# BP_devboard.net
KiCad netlist of a schematic drawn in EAGLE
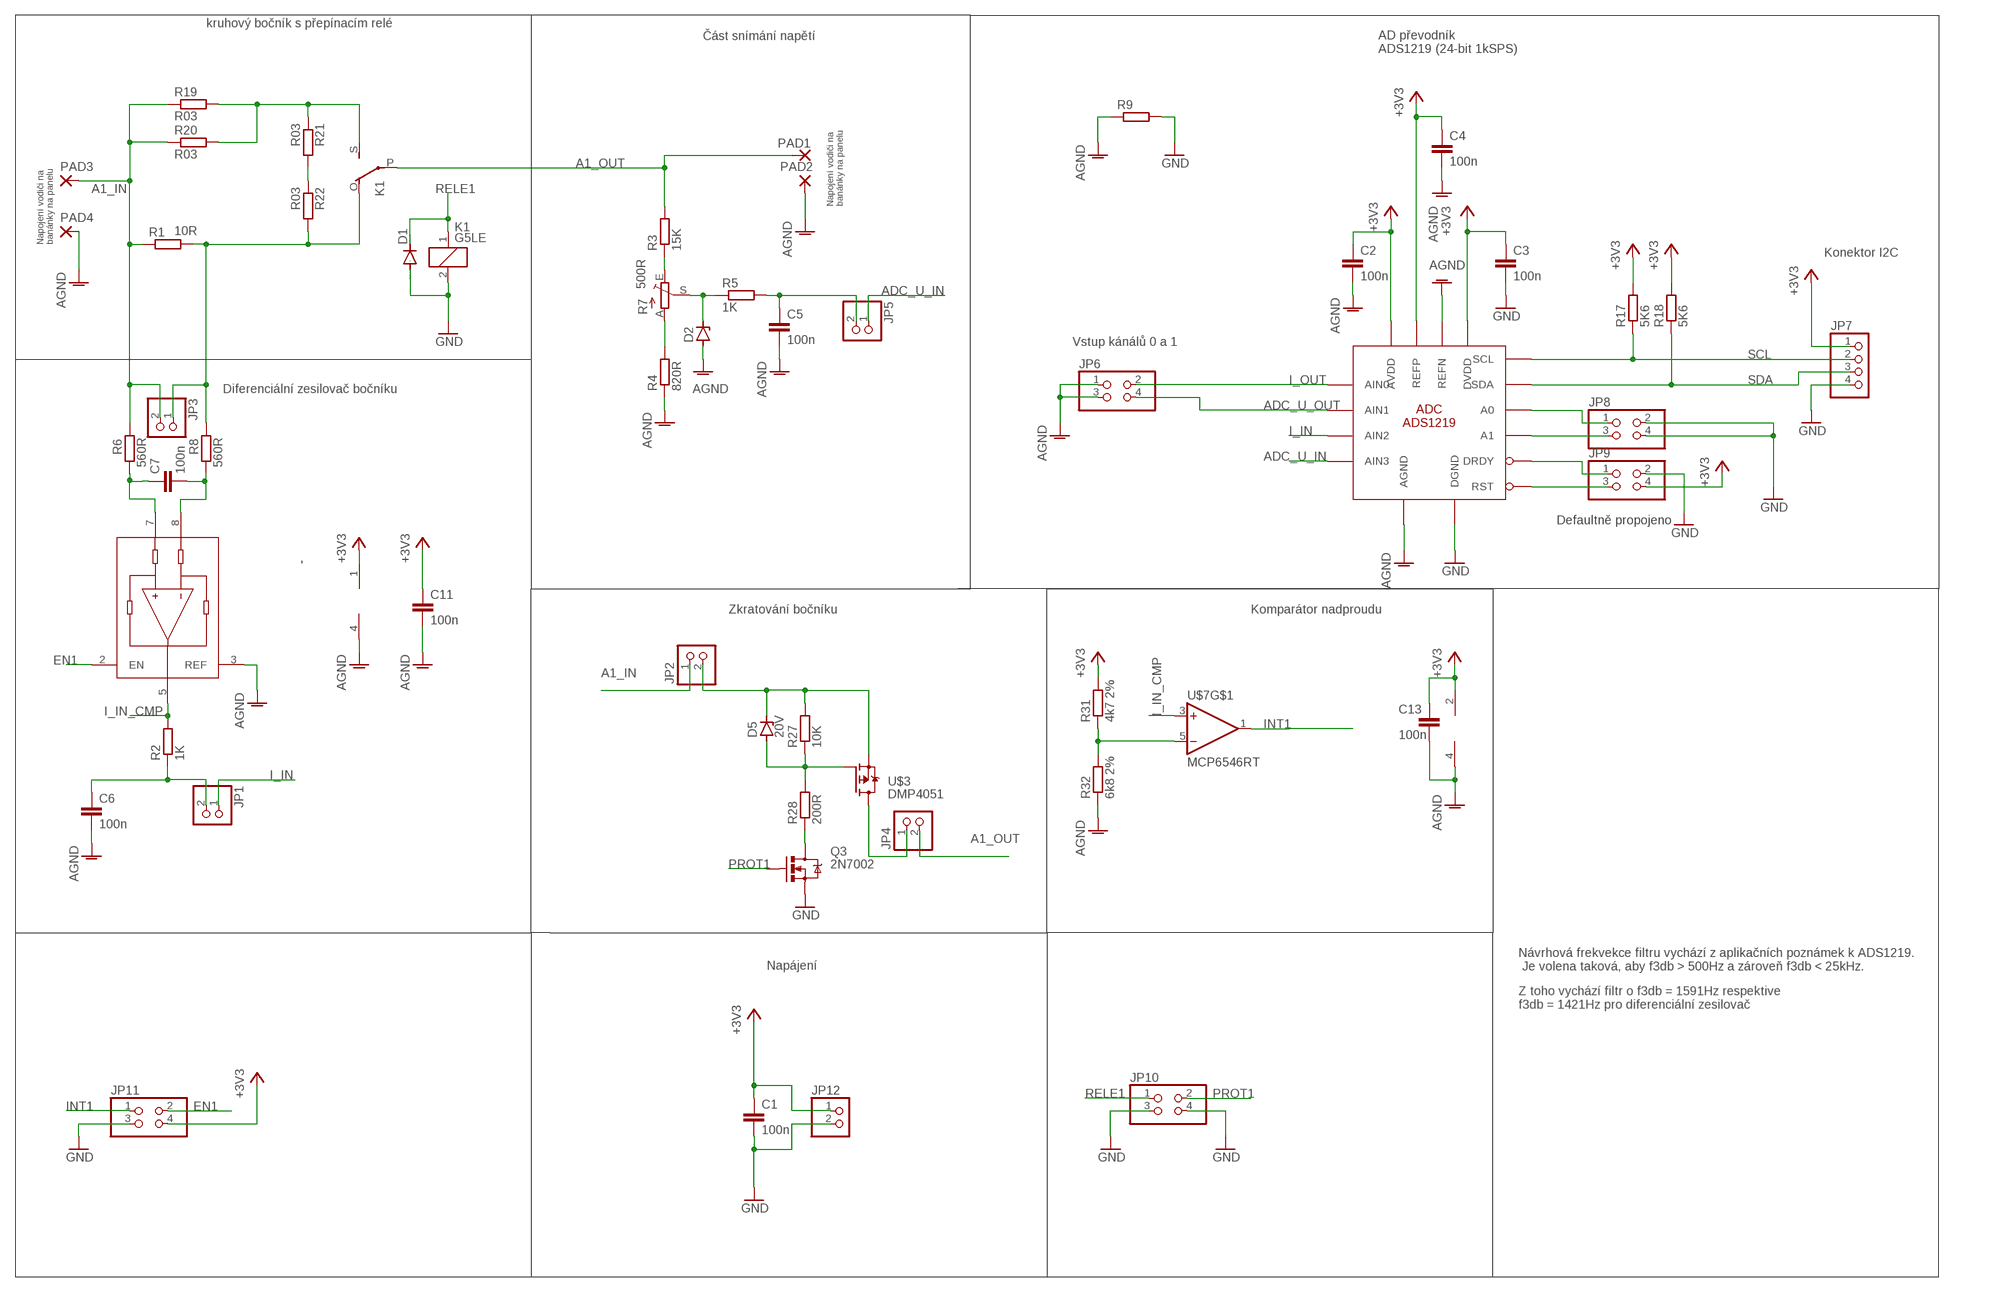
[diagram p0: schematic, sheet 1]

(export (version "E")
  (design (tool "Eeschema 10.0.6"))
  (components
    (comp (ref "C1")
      (value "100n")
      (footprint "eagle-import:C0805")
      (libsource (lib "eagle-import") (part "C-EUC0805"))
    )
    (comp (ref "C2")
      (value "100n")
      (footprint "eagle-import:C0805")
      (libsource (lib "eagle-import") (part "C-EUC0805"))
    )
    (comp (ref "C3")
      (value "100n")
      (footprint "eagle-import:C0805")
      (libsource (lib "eagle-import") (part "C-EUC0805"))
    )
    (comp (ref "C4")
      (value "100n")
      (footprint "eagle-import:C0805")
      (libsource (lib "eagle-import") (part "C-EUC0805"))
    )
    (comp (ref "C5")
      (value "100n")
      (footprint "eagle-import:C0805")
      (libsource (lib "eagle-import") (part "C-EUC0805"))
    )
    (comp (ref "C6")
      (value "100n")
      (footprint "eagle-import:C0805")
      (libsource (lib "eagle-import") (part "C-EUC0805"))
    )
    (comp (ref "C7")
      (value "100n")
      (footprint "eagle-import:C0805")
      (libsource (lib "eagle-import") (part "C-EUC0805"))
    )
    (comp (ref "C11")
      (value "100n")
      (footprint "eagle-import:C0805")
      (libsource (lib "eagle-import") (part "C-EUC0805"))
    )
    (comp (ref "C13")
      (value "100n")
      (footprint "eagle-import:C0805")
      (libsource (lib "eagle-import") (part "C-EUC0805"))
    )
    (comp (ref "D1")
      (value "DIODE-MELF-MLL41")
      (footprint "eagle-import:MELF-MLL41")
      (libsource (lib "eagle-import") (part "DIODE-MELF-MLL41"))
    )
    (comp (ref "D2")
      (value "ZENER-DIODESOD80C")
      (footprint "eagle-import:SOD80C")
      (libsource (lib "eagle-import") (part "ZENER-DIODESOD80C"))
    )
    (comp (ref "D5")
      (value "20V")
      (footprint "eagle-import:SMB")
      (libsource (lib "eagle-import") (part "ZENER-DIODESMB"))
    )
    (comp (ref "JP1")
      (value "PINHD-1X2")
      (footprint "eagle-import:1X02")
      (libsource (lib "eagle-import") (part "PINHD-1X2"))
    )
    (comp (ref "JP2")
      (value "PINHD-1X2")
      (footprint "eagle-import:1X02")
      (libsource (lib "eagle-import") (part "PINHD-1X2"))
    )
    (comp (ref "JP3")
      (value "PINHD-1X2")
      (footprint "eagle-import:1X02")
      (libsource (lib "eagle-import") (part "PINHD-1X2"))
    )
    (comp (ref "JP4")
      (value "PINHD-1X2")
      (footprint "eagle-import:1X02")
      (libsource (lib "eagle-import") (part "PINHD-1X2"))
    )
    (comp (ref "JP5")
      (value "PINHD-1X2")
      (footprint "eagle-import:1X02")
      (libsource (lib "eagle-import") (part "PINHD-1X2"))
    )
    (comp (ref "JP6")
      (value "PINHD-2X2")
      (footprint "eagle-import:2X02")
      (libsource (lib "eagle-import") (part "PINHD-2X2"))
    )
    (comp (ref "JP7")
      (value "PINHD-1X4")
      (footprint "eagle-import:1X04")
      (libsource (lib "eagle-import") (part "PINHD-1X4"))
    )
    (comp (ref "JP8")
      (value "PINHD-2X2")
      (footprint "eagle-import:2X02")
      (libsource (lib "eagle-import") (part "PINHD-2X2"))
    )
    (comp (ref "JP9")
      (value "PINHD-2X2")
      (footprint "eagle-import:2X02")
      (libsource (lib "eagle-import") (part "PINHD-2X2"))
    )
    (comp (ref "JP10")
      (value "PINHD-2X2")
      (footprint "eagle-import:2X02")
      (libsource (lib "eagle-import") (part "PINHD-2X2"))
    )
    (comp (ref "JP11")
      (value "PINHD-2X2")
      (footprint "eagle-import:2X02")
      (libsource (lib "eagle-import") (part "PINHD-2X2"))
    )
    (comp (ref "JP12")
      (value "PINHD-1X2")
      (footprint "eagle-import:1X02")
      (libsource (lib "eagle-import") (part "PINHD-1X2"))
    )
    (comp (ref "K1")
      (value "G5LE")
      (footprint "eagle-import:G5LE")
      (libsource (lib "eagle-import") (part "G5LE"))
    )
    (comp (ref "PAD1")
      (value "2,15/1,0")
      (footprint "eagle-import:2,15_1,0")
      (libsource (lib "eagle-import") (part "2,15/1,0"))
    )
    (comp (ref "PAD2")
      (value "2,15/1,0")
      (footprint "eagle-import:2,15_1,0")
      (libsource (lib "eagle-import") (part "2,15/1,0"))
    )
    (comp (ref "PAD3")
      (value "2,15/1,0")
      (footprint "eagle-import:2,15_1,0")
      (libsource (lib "eagle-import") (part "2,15/1,0"))
    )
    (comp (ref "PAD4")
      (value "2,15/1,0")
      (footprint "eagle-import:2,15_1,0")
      (libsource (lib "eagle-import") (part "2,15/1,0"))
    )
    (comp (ref "Q3")
      (value "2N7002")
      (footprint "eagle-import:SOT323")
      (libsource (lib "eagle-import") (part "MOSFET-NCHANNEL2N7002PW"))
    )
    (comp (ref "R1")
      (value "10R")
      (footprint "eagle-import:R1206")
      (libsource (lib "eagle-import") (part "R-EU_R1206"))
    )
    (comp (ref "R2")
      (value "1K")
      (footprint "eagle-import:R0805")
      (libsource (lib "eagle-import") (part "R-EU_R0805"))
    )
    (comp (ref "R3")
      (value "15K")
      (footprint "eagle-import:R0805")
      (libsource (lib "eagle-import") (part "R-EU_R0805"))
    )
    (comp (ref "R4")
      (value "820R")
      (footprint "eagle-import:R0805")
      (libsource (lib "eagle-import") (part "R-EU_R0805"))
    )
    (comp (ref "R5")
      (value "1K")
      (footprint "eagle-import:R0805")
      (libsource (lib "eagle-import") (part "R-EU_R0805"))
    )
    (comp (ref "R6")
      (value "560R")
      (footprint "eagle-import:R0805")
      (libsource (lib "eagle-import") (part "R-EU_R0805"))
    )
    (comp (ref "R7")
      (value "500R")
      (footprint "eagle-import:PT-10")
      (libsource (lib "eagle-import") (part "TRIM_EU-PT10"))
    )
    (comp (ref "R8")
      (value "560R")
      (footprint "eagle-import:R0805")
      (libsource (lib "eagle-import") (part "R-EU_R0805"))
    )
    (comp (ref "R9")
      (value "R-EU_R0805")
      (footprint "eagle-import:R0805")
      (libsource (lib "eagle-import") (part "R-EU_R0805"))
    )
    (comp (ref "R17")
      (value "5K6")
      (footprint "eagle-import:R0805")
      (libsource (lib "eagle-import") (part "R-EU_R0805"))
    )
    (comp (ref "R18")
      (value "5K6")
      (footprint "eagle-import:R0805")
      (libsource (lib "eagle-import") (part "R-EU_R0805"))
    )
    (comp (ref "R19")
      (value "R03")
      (footprint "eagle-import:R1206")
      (libsource (lib "eagle-import") (part "R-EU_R1206"))
    )
    (comp (ref "R20")
      (value "R03")
      (footprint "eagle-import:R1206")
      (libsource (lib "eagle-import") (part "R-EU_R1206"))
    )
    (comp (ref "R21")
      (value "R03")
      (footprint "eagle-import:R1206")
      (libsource (lib "eagle-import") (part "R-EU_R1206"))
    )
    (comp (ref "R22")
      (value "R03")
      (footprint "eagle-import:R1206")
      (libsource (lib "eagle-import") (part "R-EU_R1206"))
    )
    (comp (ref "R27")
      (value "10K")
      (footprint "eagle-import:R0805")
      (libsource (lib "eagle-import") (part "R-EU_R0805"))
    )
    (comp (ref "R28")
      (value "200R")
      (footprint "eagle-import:R0805")
      (libsource (lib "eagle-import") (part "R-EU_R0805"))
    )
    (comp (ref "R31")
      (value "4k7 2%")
      (footprint "eagle-import:R0805")
      (libsource (lib "eagle-import") (part "R-EU_R0805"))
    )
    (comp (ref "R32")
      (value "6k8 2%")
      (footprint "eagle-import:R0805")
      (libsource (lib "eagle-import") (part "R-EU_R0805"))
    )
    (comp (ref "U$2")
      (value "ADS1219")
      (footprint "eagle-import:TSSOP16")
      (libsource (lib "eagle-import") (part "ADS1219"))
    )
    (comp (ref "U$3")
      (value "DMP4051")
      (footprint "eagle-import:TO252")
      (libsource (lib "eagle-import") (part "DMP4051"))
    )
    (comp (ref "U$4")
      (value "INA190")
      (footprint "eagle-import:SOT-23-THIN")
      (libsource (lib "eagle-import") (part "INA190"))
    )
    (comp (ref "U$7")
      (value "MCP6546RT")
      (footprint "eagle-import:SOT23-5")
      (libsource (lib "eagle-import") (part "MCP6546RT"))
    )
  )
  (nets
    (net (code "1") (name "+3V3") (class "Default")
      (node (ref "C1") (pin "1") (pinfunction "1_1") (pintype "passive"))
      (node (ref "C11") (pin "1") (pinfunction "1_1") (pintype "passive"))
      (node (ref "C13") (pin "1") (pinfunction "1_1") (pintype "passive"))
      (node (ref "C2") (pin "1") (pinfunction "1_1") (pintype "passive"))
      (node (ref "C3") (pin "1") (pinfunction "1_1") (pintype "passive"))
      (node (ref "C4") (pin "1") (pinfunction "1_1") (pintype "passive"))
      (node (ref "JP11") (pin "4") (pinfunction "4_4") (pintype "passive"))
      (node (ref "JP12") (pin "1") (pinfunction "1_1") (pintype "passive"))
      (node (ref "JP7") (pin "1") (pinfunction "1_1") (pintype "passive"))
      (node (ref "JP9") (pin "4") (pinfunction "4_4") (pintype "passive"))
      (node (ref "R17") (pin "2") (pinfunction "2_2") (pintype "passive"))
      (node (ref "R18") (pin "2") (pinfunction "2_2") (pintype "passive"))
      (node (ref "R31") (pin "2") (pinfunction "2_2") (pintype "passive"))
      (node (ref "U$2") (pin "12") (pinfunction "AVDD_12") (pintype "power_in"))
      (node (ref "U$2") (pin "13") (pinfunction "DVDD_13") (pintype "power_in"))
      (node (ref "U$2") (pin "9") (pinfunction "REFP_9") (pintype "power_in"))
      (node (ref "U$4") (pin "1") (pinfunction "V+_1") (pintype "power_in"))
      (node (ref "U$7") (pin "2") (pinfunction "V+_2") (pintype "power_in"))
    )
    (net (code "2") (name "/A1_IN") (class "Default")
      (node (ref "JP2") (pin "1") (pinfunction "1_1") (pintype "passive"))
      (node (ref "JP3") (pin "2") (pinfunction "2_2") (pintype "passive"))
      (node (ref "PAD3") (pin "1") (pinfunction "P_1") (pintype "passive"))
      (node (ref "R1") (pin "1") (pinfunction "1_1") (pintype "passive"))
      (node (ref "R19") (pin "1") (pinfunction "1_1") (pintype "passive"))
      (node (ref "R20") (pin "1") (pinfunction "1_1") (pintype "passive"))
      (node (ref "R6") (pin "2") (pinfunction "2_2") (pintype "passive"))
    )
    (net (code "3") (name "/A1_OUT") (class "Default")
      (node (ref "JP4") (pin "2") (pinfunction "2_2") (pintype "passive"))
      (node (ref "K1") (pin "P") (pinfunction "P_P") (pintype "passive"))
      (node (ref "PAD1") (pin "1") (pinfunction "P_1") (pintype "passive"))
      (node (ref "R3") (pin "2") (pinfunction "2_2") (pintype "passive"))
    )
    (net (code "4") (name "/ADC_U_IN") (class "Default")
      (node (ref "JP5") (pin "1") (pinfunction "1_1") (pintype "passive"))
      (node (ref "U$2") (pin "6") (pinfunction "AIN3_6") (pintype "input"))
    )
    (net (code "5") (name "/ADC_U_OUT") (class "Default")
      (node (ref "JP6") (pin "4") (pinfunction "4_4") (pintype "passive"))
      (node (ref "U$2") (pin "10") (pinfunction "AIN1_10") (pintype "input"))
    )
    (net (code "6") (name "/EN1") (class "Default")
      (node (ref "JP11") (pin "2") (pinfunction "2_2") (pintype "passive"))
      (node (ref "U$4") (pin "2") (pinfunction "EN_2") (pintype "input"))
    )
    (net (code "7") (name "/INT1") (class "Default")
      (node (ref "JP11") (pin "1") (pinfunction "1_1") (pintype "passive"))
      (node (ref "U$7") (pin "1") (pinfunction "OUT_1") (pintype "output"))
    )
    (net (code "8") (name "/I_IN") (class "Default")
      (node (ref "JP1") (pin "1") (pinfunction "1_1") (pintype "passive"))
      (node (ref "U$2") (pin "7") (pinfunction "AIN2_7") (pintype "input"))
    )
    (net (code "9") (name "/I_IN_CMP") (class "Default")
      (node (ref "R2") (pin "2") (pinfunction "2_2") (pintype "passive"))
      (node (ref "U$4") (pin "5") (pinfunction "P$4_5") (pintype "output"))
      (node (ref "U$7") (pin "3") (pinfunction "+IN_3") (pintype "input"))
    )
    (net (code "10") (name "/I_OUT") (class "Default")
      (node (ref "JP6") (pin "2") (pinfunction "2_2") (pintype "passive"))
      (node (ref "U$2") (pin "11") (pinfunction "AIN0_11") (pintype "input"))
    )
    (net (code "11") (name "/PROT1") (class "Default")
      (node (ref "JP10") (pin "2") (pinfunction "2_2") (pintype "passive"))
      (node (ref "Q3") (pin "1") (pinfunction "G_1") (pintype "passive"))
    )
    (net (code "12") (name "/RELE1") (class "Default")
      (node (ref "D1") (pin "C") (pinfunction "C_C") (pintype "passive"))
      (node (ref "JP10") (pin "1") (pinfunction "1_1") (pintype "passive"))
      (node (ref "K1") (pin "1") (pinfunction "1_1") (pintype "passive"))
    )
    (net (code "13") (name "/SCL") (class "Default")
      (node (ref "JP7") (pin "2") (pinfunction "2_2") (pintype "passive"))
      (node (ref "R17") (pin "1") (pinfunction "1_1") (pintype "passive"))
      (node (ref "U$2") (pin "16") (pinfunction "SCL_16") (pintype "bidirectional"))
    )
    (net (code "14") (name "/SDA") (class "Default")
      (node (ref "JP7") (pin "3") (pinfunction "3_3") (pintype "passive"))
      (node (ref "R18") (pin "1") (pinfunction "1_1") (pintype "passive"))
      (node (ref "U$2") (pin "15") (pinfunction "SDA_15") (pintype "bidirectional"))
    )
    (net (code "15") (name "AGND") (class "Default")
      (node (ref "C11") (pin "2") (pinfunction "2_2") (pintype "passive"))
      (node (ref "C13") (pin "2") (pinfunction "2_2") (pintype "passive"))
      (node (ref "C2") (pin "2") (pinfunction "2_2") (pintype "passive"))
      (node (ref "C4") (pin "2") (pinfunction "2_2") (pintype "passive"))
      (node (ref "C5") (pin "2") (pinfunction "2_2") (pintype "passive"))
      (node (ref "C6") (pin "2") (pinfunction "2_2") (pintype "passive"))
      (node (ref "D2") (pin "A") (pinfunction "A_A") (pintype "passive"))
      (node (ref "JP6") (pin "1") (pinfunction "1_1") (pintype "passive"))
      (node (ref "JP6") (pin "3") (pinfunction "3_3") (pintype "passive"))
      (node (ref "PAD2") (pin "1") (pinfunction "P_1") (pintype "passive"))
      (node (ref "PAD4") (pin "1") (pinfunction "P_1") (pintype "passive"))
      (node (ref "R32") (pin "1") (pinfunction "1_1") (pintype "passive"))
      (node (ref "R4") (pin "1") (pinfunction "1_1") (pintype "passive"))
      (node (ref "R9") (pin "1") (pinfunction "1_1") (pintype "passive"))
      (node (ref "U$2") (pin "5") (pinfunction "AGND_5") (pintype "power_in"))
      (node (ref "U$2") (pin "8") (pinfunction "REFN_8") (pintype "power_in"))
      (node (ref "U$4") (pin "3") (pinfunction "REF_3") (pintype "input"))
      (node (ref "U$4") (pin "4") (pinfunction "V-_4") (pintype "power_in"))
      (node (ref "U$7") (pin "4") (pinfunction "V-_4") (pintype "power_in"))
    )
    (net (code "16") (name "GND") (class "Default")
      (node (ref "C1") (pin "2") (pinfunction "2_2") (pintype "passive"))
      (node (ref "C3") (pin "2") (pinfunction "2_2") (pintype "passive"))
      (node (ref "D1") (pin "A") (pinfunction "A_A") (pintype "passive"))
      (node (ref "JP10") (pin "3") (pinfunction "3_3") (pintype "passive"))
      (node (ref "JP10") (pin "4") (pinfunction "4_4") (pintype "passive"))
      (node (ref "JP11") (pin "3") (pinfunction "3_3") (pintype "passive"))
      (node (ref "JP12") (pin "2") (pinfunction "2_2") (pintype "passive"))
      (node (ref "JP7") (pin "4") (pinfunction "4_4") (pintype "passive"))
      (node (ref "JP8") (pin "2") (pinfunction "2_2") (pintype "passive"))
      (node (ref "JP8") (pin "4") (pinfunction "4_4") (pintype "passive"))
      (node (ref "JP9") (pin "2") (pinfunction "2_2") (pintype "passive"))
      (node (ref "K1") (pin "2") (pinfunction "2_2") (pintype "passive"))
      (node (ref "Q3") (pin "2") (pinfunction "S_2") (pintype "passive"))
      (node (ref "R9") (pin "2") (pinfunction "2_2") (pintype "passive"))
      (node (ref "U$2") (pin "4") (pinfunction "DGND_4") (pintype "power_in"))
    )
    (net (code "17") (name "Net-(C5-Pad1)") (class "Default")
      (node (ref "C5") (pin "1") (pinfunction "1_1") (pintype "passive"))
      (node (ref "JP5") (pin "2") (pinfunction "2_2") (pintype "passive"))
      (node (ref "R5") (pin "2") (pinfunction "2_2") (pintype "passive"))
    )
    (net (code "18") (name "Net-(C6-Pad1)") (class "Default")
      (node (ref "C6") (pin "1") (pinfunction "1_1") (pintype "passive"))
      (node (ref "JP1") (pin "2") (pinfunction "2_2") (pintype "passive"))
      (node (ref "R2") (pin "1") (pinfunction "1_1") (pintype "passive"))
    )
    (net (code "19") (name "Net-(D2-PadC)") (class "Default")
      (node (ref "D2") (pin "C") (pinfunction "C_C") (pintype "passive"))
      (node (ref "R5") (pin "1") (pinfunction "1_1") (pintype "passive"))
      (node (ref "R7") (pin "S") (pinfunction "S_S") (pintype "passive"))
    )
    (net (code "20") (name "Net-(JP3-Pad1)") (class "Default")
      (node (ref "JP3") (pin "1") (pinfunction "1_1") (pintype "passive"))
      (node (ref "K1") (pin "O") (pinfunction "O_O") (pintype "passive"))
      (node (ref "R1") (pin "2") (pinfunction "2_2") (pintype "passive"))
      (node (ref "R22") (pin "2") (pinfunction "2_2") (pintype "passive"))
      (node (ref "R8") (pin "2") (pinfunction "2_2") (pintype "passive"))
    )
    (net (code "21") (name "Net-(K1-PadS)") (class "Default")
      (node (ref "K1") (pin "S") (pinfunction "S_S") (pintype "passive"))
      (node (ref "R19") (pin "2") (pinfunction "2_2") (pintype "passive"))
      (node (ref "R20") (pin "2") (pinfunction "2_2") (pintype "passive"))
      (node (ref "R21") (pin "1") (pinfunction "1_1") (pintype "passive"))
    )
    (net (code "22") (name "Net-(Q3-D)") (class "Default")
      (node (ref "Q3") (pin "3") (pinfunction "D_3") (pintype "passive"))
      (node (ref "R28") (pin "1") (pinfunction "1_1") (pintype "passive"))
    )
    (net (code "23") (name "Net-(R3-Pad1)") (class "Default")
      (node (ref "R3") (pin "1") (pinfunction "1_1") (pintype "passive"))
      (node (ref "R7") (pin "E") (pinfunction "E_E") (pintype "passive"))
    )
    (net (code "24") (name "Net-(R4-Pad2)") (class "Default")
      (node (ref "R4") (pin "2") (pinfunction "2_2") (pintype "passive"))
      (node (ref "R7") (pin "A") (pinfunction "A_A") (pintype "passive"))
    )
    (net (code "25") (name "Net-(R21-Pad2)") (class "Default")
      (node (ref "R21") (pin "2") (pinfunction "2_2") (pintype "passive"))
      (node (ref "R22") (pin "1") (pinfunction "1_1") (pintype "passive"))
    )
    (net (code "26") (name "Net-(U$2-A0)") (class "Default")
      (node (ref "JP8") (pin "1") (pinfunction "1_1") (pintype "passive"))
      (node (ref "U$2") (pin "1") (pinfunction "A0_1") (pintype "input"))
    )
    (net (code "27") (name "Net-(U$2-A1)") (class "Default")
      (node (ref "JP8") (pin "3") (pinfunction "3_3") (pintype "passive"))
      (node (ref "U$2") (pin "2") (pinfunction "A1_2") (pintype "input"))
    )
    (net (code "28") (name "Net-(U$2-DRDY)") (class "Default")
      (node (ref "JP9") (pin "1") (pinfunction "1_1") (pintype "passive"))
      (node (ref "U$2") (pin "14") (pinfunction "DRDY_14") (pintype "output"))
    )
    (net (code "29") (name "Net-(U$2-RST)") (class "Default")
      (node (ref "JP9") (pin "3") (pinfunction "3_3") (pintype "passive"))
      (node (ref "U$2") (pin "3") (pinfunction "RST_3") (pintype "input"))
    )
    (net (code "30") (name "Net-(U$3-D)") (class "Default")
      (node (ref "JP4") (pin "1") (pinfunction "1_1") (pintype "passive"))
      (node (ref "U$3") (pin "3") (pinfunction "D_3") (pintype "passive"))
    )
    (net (code "31") (name "Net-(U$3-G)") (class "Default")
      (node (ref "D5") (pin "A") (pinfunction "A_A") (pintype "passive"))
      (node (ref "R27") (pin "1") (pinfunction "1_1") (pintype "passive"))
      (node (ref "R28") (pin "2") (pinfunction "2_2") (pintype "passive"))
      (node (ref "U$3") (pin "1") (pinfunction "G_1") (pintype "passive"))
    )
    (net (code "32") (name "Net-(U$3-S)") (class "Default")
      (node (ref "D5") (pin "C") (pinfunction "C_C") (pintype "passive"))
      (node (ref "JP2") (pin "2") (pinfunction "2_2") (pintype "passive"))
      (node (ref "R27") (pin "2") (pinfunction "2_2") (pintype "passive"))
      (node (ref "U$3") (pin "2") (pinfunction "S_2") (pintype "passive"))
    )
    (net (code "33") (name "Net-(U$4A-+)") (class "Default")
      (node (ref "C7") (pin "1") (pinfunction "1_1") (pintype "passive"))
      (node (ref "R6") (pin "1") (pinfunction "1_1") (pintype "passive"))
      (node (ref "U$4") (pin "7") (pinfunction "+_7") (pintype "input"))
    )
    (net (code "34") (name "Net-(U$4A--)") (class "Default")
      (node (ref "C7") (pin "2") (pinfunction "2_2") (pintype "passive"))
      (node (ref "R8") (pin "1") (pinfunction "1_1") (pintype "passive"))
      (node (ref "U$4") (pin "8") (pinfunction "-_8") (pintype "input"))
    )
    (net (code "35") (name "Net-(U$7A--IN)") (class "Default")
      (node (ref "R31") (pin "1") (pinfunction "1_1") (pintype "passive"))
      (node (ref "R32") (pin "2") (pinfunction "2_2") (pintype "passive"))
      (node (ref "U$7") (pin "5") (pinfunction "-IN_5") (pintype "input"))
    )
  )
)
